# dot-reader.net
KiCad netlist of a schematic drawn in EAGLE
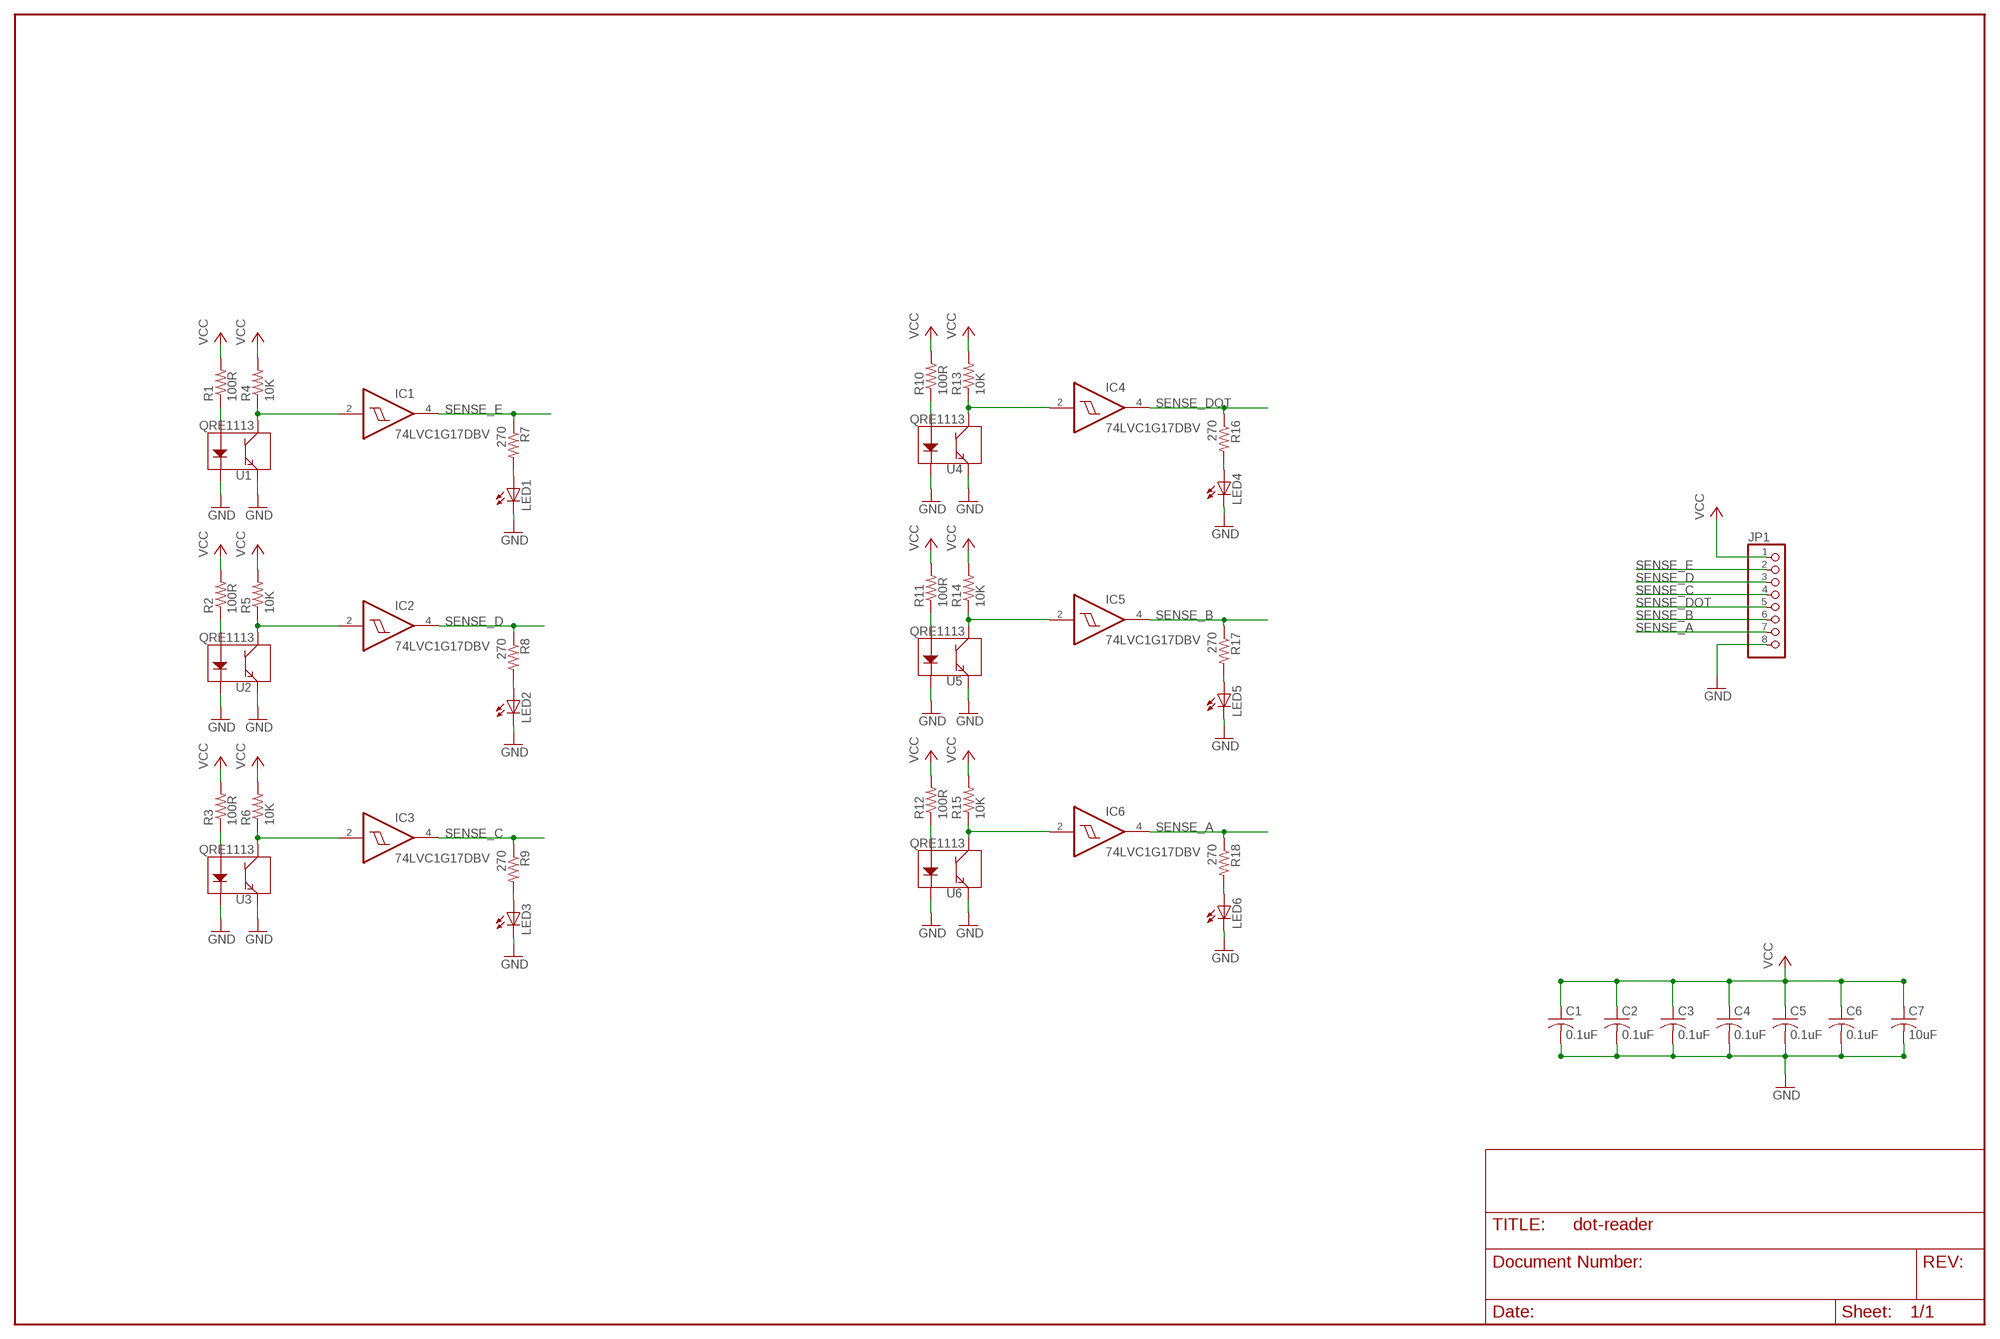
[diagram p0: schematic, sheet 1]

(export (version "E")
  (design (tool "Eeschema 10.0.6"))
  (components
    (comp (ref "C1")
      (value "0.1uF")
      (footprint "eagle-import:C0603")
      (libsource (lib "eagle-import") (part "C-USC0603"))
    )
    (comp (ref "C2")
      (value "0.1uF")
      (footprint "eagle-import:C0603")
      (libsource (lib "eagle-import") (part "C-USC0603"))
    )
    (comp (ref "C3")
      (value "0.1uF")
      (footprint "eagle-import:C0603")
      (libsource (lib "eagle-import") (part "C-USC0603"))
    )
    (comp (ref "C4")
      (value "0.1uF")
      (footprint "eagle-import:C0603")
      (libsource (lib "eagle-import") (part "C-USC0603"))
    )
    (comp (ref "C5")
      (value "0.1uF")
      (footprint "eagle-import:C0603")
      (libsource (lib "eagle-import") (part "C-USC0603"))
    )
    (comp (ref "C6")
      (value "0.1uF")
      (footprint "eagle-import:C0603")
      (libsource (lib "eagle-import") (part "C-USC0603"))
    )
    (comp (ref "C7")
      (value "10uF")
      (footprint "eagle-import:C0805")
      (libsource (lib "eagle-import") (part "C-USC0805"))
    )
    (comp (ref "IC1")
      (value "74LVC1G17DBV")
      (footprint "eagle-import:SOT23-5")
      (libsource (lib "eagle-import") (part "741G17DBVLVC"))
    )
    (comp (ref "IC2")
      (value "74LVC1G17DBV")
      (footprint "eagle-import:SOT23-5")
      (libsource (lib "eagle-import") (part "741G17DBVLVC"))
    )
    (comp (ref "IC3")
      (value "74LVC1G17DBV")
      (footprint "eagle-import:SOT23-5")
      (libsource (lib "eagle-import") (part "741G17DBVLVC"))
    )
    (comp (ref "IC4")
      (value "74LVC1G17DBV")
      (footprint "eagle-import:SOT23-5")
      (libsource (lib "eagle-import") (part "741G17DBVLVC"))
    )
    (comp (ref "IC5")
      (value "74LVC1G17DBV")
      (footprint "eagle-import:SOT23-5")
      (libsource (lib "eagle-import") (part "741G17DBVLVC"))
    )
    (comp (ref "IC6")
      (value "74LVC1G17DBV")
      (footprint "eagle-import:SOT23-5")
      (libsource (lib "eagle-import") (part "741G17DBVLVC"))
    )
    (comp (ref "JP1")
      (value "PINHD-1X8")
      (footprint "eagle-import:1X08")
      (libsource (lib "eagle-import") (part "PINHD-1X8"))
    )
    (comp (ref "LED1")
      (value "LEDCHIP-LED0805")
      (footprint "eagle-import:CHIP-LED0805")
      (libsource (lib "eagle-import") (part "LEDCHIP-LED0805"))
    )
    (comp (ref "LED2")
      (value "LEDCHIP-LED0805")
      (footprint "eagle-import:CHIP-LED0805")
      (libsource (lib "eagle-import") (part "LEDCHIP-LED0805"))
    )
    (comp (ref "LED3")
      (value "LEDCHIP-LED0805")
      (footprint "eagle-import:CHIP-LED0805")
      (libsource (lib "eagle-import") (part "LEDCHIP-LED0805"))
    )
    (comp (ref "LED4")
      (value "LEDCHIP-LED0805")
      (footprint "eagle-import:CHIP-LED0805")
      (libsource (lib "eagle-import") (part "LEDCHIP-LED0805"))
    )
    (comp (ref "LED5")
      (value "LEDCHIP-LED0805")
      (footprint "eagle-import:CHIP-LED0805")
      (libsource (lib "eagle-import") (part "LEDCHIP-LED0805"))
    )
    (comp (ref "LED6")
      (value "LEDCHIP-LED0805")
      (footprint "eagle-import:CHIP-LED0805")
      (libsource (lib "eagle-import") (part "LEDCHIP-LED0805"))
    )
    (comp (ref "R1")
      (value "100R")
      (footprint "eagle-import:M0805")
      (libsource (lib "eagle-import") (part "R-US_M0805"))
    )
    (comp (ref "R2")
      (value "100R")
      (footprint "eagle-import:M0805")
      (libsource (lib "eagle-import") (part "R-US_M0805"))
    )
    (comp (ref "R3")
      (value "100R")
      (footprint "eagle-import:M0805")
      (libsource (lib "eagle-import") (part "R-US_M0805"))
    )
    (comp (ref "R4")
      (value "10K")
      (footprint "eagle-import:M0805")
      (libsource (lib "eagle-import") (part "R-US_M0805"))
    )
    (comp (ref "R5")
      (value "10K")
      (footprint "eagle-import:M0805")
      (libsource (lib "eagle-import") (part "R-US_M0805"))
    )
    (comp (ref "R6")
      (value "10K")
      (footprint "eagle-import:M0805")
      (libsource (lib "eagle-import") (part "R-US_M0805"))
    )
    (comp (ref "R7")
      (value "270")
      (footprint "eagle-import:R0805")
      (libsource (lib "eagle-import") (part "R-US_R0805"))
    )
    (comp (ref "R8")
      (value "270")
      (footprint "eagle-import:R0805")
      (libsource (lib "eagle-import") (part "R-US_R0805"))
    )
    (comp (ref "R9")
      (value "270")
      (footprint "eagle-import:R0805")
      (libsource (lib "eagle-import") (part "R-US_R0805"))
    )
    (comp (ref "R10")
      (value "100R")
      (footprint "eagle-import:M0805")
      (libsource (lib "eagle-import") (part "R-US_M0805"))
    )
    (comp (ref "R11")
      (value "100R")
      (footprint "eagle-import:M0805")
      (libsource (lib "eagle-import") (part "R-US_M0805"))
    )
    (comp (ref "R12")
      (value "100R")
      (footprint "eagle-import:M0805")
      (libsource (lib "eagle-import") (part "R-US_M0805"))
    )
    (comp (ref "R13")
      (value "10K")
      (footprint "eagle-import:M0805")
      (libsource (lib "eagle-import") (part "R-US_M0805"))
    )
    (comp (ref "R14")
      (value "10K")
      (footprint "eagle-import:M0805")
      (libsource (lib "eagle-import") (part "R-US_M0805"))
    )
    (comp (ref "R15")
      (value "10K")
      (footprint "eagle-import:M0805")
      (libsource (lib "eagle-import") (part "R-US_M0805"))
    )
    (comp (ref "R16")
      (value "270")
      (footprint "eagle-import:R0805")
      (libsource (lib "eagle-import") (part "R-US_R0805"))
    )
    (comp (ref "R17")
      (value "270")
      (footprint "eagle-import:R0805")
      (libsource (lib "eagle-import") (part "R-US_R0805"))
    )
    (comp (ref "R18")
      (value "270")
      (footprint "eagle-import:R0805")
      (libsource (lib "eagle-import") (part "R-US_R0805"))
    )
    (comp (ref "U1")
      (value "QRE1113")
      (footprint "eagle-import:QRE1113")
      (libsource (lib "eagle-import") (part "QRE1113"))
    )
    (comp (ref "U2")
      (value "QRE1113")
      (footprint "eagle-import:QRE1113")
      (libsource (lib "eagle-import") (part "QRE1113"))
    )
    (comp (ref "U3")
      (value "QRE1113")
      (footprint "eagle-import:QRE1113")
      (libsource (lib "eagle-import") (part "QRE1113"))
    )
    (comp (ref "U4")
      (value "QRE1113")
      (footprint "eagle-import:QRE1113")
      (libsource (lib "eagle-import") (part "QRE1113"))
    )
    (comp (ref "U5")
      (value "QRE1113")
      (footprint "eagle-import:QRE1113")
      (libsource (lib "eagle-import") (part "QRE1113"))
    )
    (comp (ref "U6")
      (value "QRE1113")
      (footprint "eagle-import:QRE1113")
      (libsource (lib "eagle-import") (part "QRE1113"))
    )
  )
  (nets
    (net (code "1") (name "/SENSE_A") (class "Default")
      (node (ref "IC6") (pin "4") (pinfunction "O_4") (pintype "output"))
      (node (ref "JP1") (pin "7") (pinfunction "7_7") (pintype "passive"))
      (node (ref "R18") (pin "1") (pinfunction "1_1") (pintype "passive"))
    )
    (net (code "2") (name "/SENSE_B") (class "Default")
      (node (ref "IC5") (pin "4") (pinfunction "O_4") (pintype "output"))
      (node (ref "JP1") (pin "6") (pinfunction "6_6") (pintype "passive"))
      (node (ref "R17") (pin "1") (pinfunction "1_1") (pintype "passive"))
    )
    (net (code "3") (name "/SENSE_C") (class "Default")
      (node (ref "IC3") (pin "4") (pinfunction "O_4") (pintype "output"))
      (node (ref "JP1") (pin "4") (pinfunction "4_4") (pintype "passive"))
      (node (ref "R9") (pin "1") (pinfunction "1_1") (pintype "passive"))
    )
    (net (code "4") (name "/SENSE_D") (class "Default")
      (node (ref "IC2") (pin "4") (pinfunction "O_4") (pintype "output"))
      (node (ref "JP1") (pin "3") (pinfunction "3_3") (pintype "passive"))
      (node (ref "R8") (pin "1") (pinfunction "1_1") (pintype "passive"))
    )
    (net (code "5") (name "/SENSE_DOT") (class "Default")
      (node (ref "IC4") (pin "4") (pinfunction "O_4") (pintype "output"))
      (node (ref "JP1") (pin "5") (pinfunction "5_5") (pintype "passive"))
      (node (ref "R16") (pin "1") (pinfunction "1_1") (pintype "passive"))
    )
    (net (code "6") (name "/SENSE_E") (class "Default")
      (node (ref "IC1") (pin "4") (pinfunction "O_4") (pintype "output"))
      (node (ref "JP1") (pin "2") (pinfunction "2_2") (pintype "passive"))
      (node (ref "R7") (pin "1") (pinfunction "1_1") (pintype "passive"))
    )
    (net (code "7") (name "GND") (class "Default")
      (node (ref "C1") (pin "2") (pinfunction "2_2") (pintype "passive"))
      (node (ref "C2") (pin "2") (pinfunction "2_2") (pintype "passive"))
      (node (ref "C3") (pin "2") (pinfunction "2_2") (pintype "passive"))
      (node (ref "C4") (pin "2") (pinfunction "2_2") (pintype "passive"))
      (node (ref "C5") (pin "2") (pinfunction "2_2") (pintype "passive"))
      (node (ref "C6") (pin "2") (pinfunction "2_2") (pintype "passive"))
      (node (ref "C7") (pin "2") (pinfunction "2_2") (pintype "passive"))
      (node (ref "JP1") (pin "8") (pinfunction "8_8") (pintype "passive"))
      (node (ref "LED1") (pin "C") (pinfunction "C_C") (pintype "passive"))
      (node (ref "LED2") (pin "C") (pinfunction "C_C") (pintype "passive"))
      (node (ref "LED3") (pin "C") (pinfunction "C_C") (pintype "passive"))
      (node (ref "LED4") (pin "C") (pinfunction "C_C") (pintype "passive"))
      (node (ref "LED5") (pin "C") (pinfunction "C_C") (pintype "passive"))
      (node (ref "LED6") (pin "C") (pinfunction "C_C") (pintype "passive"))
      (node (ref "U1") (pin "2") (pinfunction "K_2") (pintype "bidirectional"))
      (node (ref "U1") (pin "4") (pinfunction "E_4") (pintype "bidirectional"))
      (node (ref "U2") (pin "2") (pinfunction "K_2") (pintype "bidirectional"))
      (node (ref "U2") (pin "4") (pinfunction "E_4") (pintype "bidirectional"))
      (node (ref "U3") (pin "2") (pinfunction "K_2") (pintype "bidirectional"))
      (node (ref "U3") (pin "4") (pinfunction "E_4") (pintype "bidirectional"))
      (node (ref "U4") (pin "2") (pinfunction "K_2") (pintype "bidirectional"))
      (node (ref "U4") (pin "4") (pinfunction "E_4") (pintype "bidirectional"))
      (node (ref "U5") (pin "2") (pinfunction "K_2") (pintype "bidirectional"))
      (node (ref "U5") (pin "4") (pinfunction "E_4") (pintype "bidirectional"))
      (node (ref "U6") (pin "2") (pinfunction "K_2") (pintype "bidirectional"))
      (node (ref "U6") (pin "4") (pinfunction "E_4") (pintype "bidirectional"))
    )
    (net (code "8") (name "Net-(IC1A-I)") (class "Default")
      (node (ref "IC1") (pin "2") (pinfunction "I_2") (pintype "input"))
      (node (ref "R4") (pin "1") (pinfunction "1_1") (pintype "passive"))
      (node (ref "U1") (pin "3") (pinfunction "C_3") (pintype "bidirectional"))
    )
    (net (code "9") (name "Net-(IC2A-I)") (class "Default")
      (node (ref "IC2") (pin "2") (pinfunction "I_2") (pintype "input"))
      (node (ref "R5") (pin "1") (pinfunction "1_1") (pintype "passive"))
      (node (ref "U2") (pin "3") (pinfunction "C_3") (pintype "bidirectional"))
    )
    (net (code "10") (name "Net-(IC3A-I)") (class "Default")
      (node (ref "IC3") (pin "2") (pinfunction "I_2") (pintype "input"))
      (node (ref "R6") (pin "1") (pinfunction "1_1") (pintype "passive"))
      (node (ref "U3") (pin "3") (pinfunction "C_3") (pintype "bidirectional"))
    )
    (net (code "11") (name "Net-(IC4A-I)") (class "Default")
      (node (ref "IC4") (pin "2") (pinfunction "I_2") (pintype "input"))
      (node (ref "R13") (pin "1") (pinfunction "1_1") (pintype "passive"))
      (node (ref "U4") (pin "3") (pinfunction "C_3") (pintype "bidirectional"))
    )
    (net (code "12") (name "Net-(IC5A-I)") (class "Default")
      (node (ref "IC5") (pin "2") (pinfunction "I_2") (pintype "input"))
      (node (ref "R14") (pin "1") (pinfunction "1_1") (pintype "passive"))
      (node (ref "U5") (pin "3") (pinfunction "C_3") (pintype "bidirectional"))
    )
    (net (code "13") (name "Net-(IC6A-I)") (class "Default")
      (node (ref "IC6") (pin "2") (pinfunction "I_2") (pintype "input"))
      (node (ref "R15") (pin "1") (pinfunction "1_1") (pintype "passive"))
      (node (ref "U6") (pin "3") (pinfunction "C_3") (pintype "bidirectional"))
    )
    (net (code "14") (name "Net-(LED1-PadA)") (class "Default")
      (node (ref "LED1") (pin "A") (pinfunction "A_A") (pintype "passive"))
      (node (ref "R7") (pin "2") (pinfunction "2_2") (pintype "passive"))
    )
    (net (code "15") (name "Net-(LED2-PadA)") (class "Default")
      (node (ref "LED2") (pin "A") (pinfunction "A_A") (pintype "passive"))
      (node (ref "R8") (pin "2") (pinfunction "2_2") (pintype "passive"))
    )
    (net (code "16") (name "Net-(LED3-PadA)") (class "Default")
      (node (ref "LED3") (pin "A") (pinfunction "A_A") (pintype "passive"))
      (node (ref "R9") (pin "2") (pinfunction "2_2") (pintype "passive"))
    )
    (net (code "17") (name "Net-(LED4-PadA)") (class "Default")
      (node (ref "LED4") (pin "A") (pinfunction "A_A") (pintype "passive"))
      (node (ref "R16") (pin "2") (pinfunction "2_2") (pintype "passive"))
    )
    (net (code "18") (name "Net-(LED5-PadA)") (class "Default")
      (node (ref "LED5") (pin "A") (pinfunction "A_A") (pintype "passive"))
      (node (ref "R17") (pin "2") (pinfunction "2_2") (pintype "passive"))
    )
    (net (code "19") (name "Net-(LED6-PadA)") (class "Default")
      (node (ref "LED6") (pin "A") (pinfunction "A_A") (pintype "passive"))
      (node (ref "R18") (pin "2") (pinfunction "2_2") (pintype "passive"))
    )
    (net (code "20") (name "Net-(U1-A)") (class "Default")
      (node (ref "R1") (pin "1") (pinfunction "1_1") (pintype "passive"))
      (node (ref "U1") (pin "1") (pinfunction "A_1") (pintype "bidirectional"))
    )
    (net (code "21") (name "Net-(U2-A)") (class "Default")
      (node (ref "R2") (pin "1") (pinfunction "1_1") (pintype "passive"))
      (node (ref "U2") (pin "1") (pinfunction "A_1") (pintype "bidirectional"))
    )
    (net (code "22") (name "Net-(U3-A)") (class "Default")
      (node (ref "R3") (pin "1") (pinfunction "1_1") (pintype "passive"))
      (node (ref "U3") (pin "1") (pinfunction "A_1") (pintype "bidirectional"))
    )
    (net (code "23") (name "Net-(U4-A)") (class "Default")
      (node (ref "R10") (pin "1") (pinfunction "1_1") (pintype "passive"))
      (node (ref "U4") (pin "1") (pinfunction "A_1") (pintype "bidirectional"))
    )
    (net (code "24") (name "Net-(U5-A)") (class "Default")
      (node (ref "R11") (pin "1") (pinfunction "1_1") (pintype "passive"))
      (node (ref "U5") (pin "1") (pinfunction "A_1") (pintype "bidirectional"))
    )
    (net (code "25") (name "Net-(U6-A)") (class "Default")
      (node (ref "R12") (pin "1") (pinfunction "1_1") (pintype "passive"))
      (node (ref "U6") (pin "1") (pinfunction "A_1") (pintype "bidirectional"))
    )
    (net (code "26") (name "VCC") (class "Default")
      (node (ref "C1") (pin "1") (pinfunction "1_1") (pintype "passive"))
      (node (ref "C2") (pin "1") (pinfunction "1_1") (pintype "passive"))
      (node (ref "C3") (pin "1") (pinfunction "1_1") (pintype "passive"))
      (node (ref "C4") (pin "1") (pinfunction "1_1") (pintype "passive"))
      (node (ref "C5") (pin "1") (pinfunction "1_1") (pintype "passive"))
      (node (ref "C6") (pin "1") (pinfunction "1_1") (pintype "passive"))
      (node (ref "C7") (pin "1") (pinfunction "1_1") (pintype "passive"))
      (node (ref "JP1") (pin "1") (pinfunction "1_1") (pintype "passive"))
      (node (ref "R1") (pin "2") (pinfunction "2_2") (pintype "passive"))
      (node (ref "R10") (pin "2") (pinfunction "2_2") (pintype "passive"))
      (node (ref "R11") (pin "2") (pinfunction "2_2") (pintype "passive"))
      (node (ref "R12") (pin "2") (pinfunction "2_2") (pintype "passive"))
      (node (ref "R13") (pin "2") (pinfunction "2_2") (pintype "passive"))
      (node (ref "R14") (pin "2") (pinfunction "2_2") (pintype "passive"))
      (node (ref "R15") (pin "2") (pinfunction "2_2") (pintype "passive"))
      (node (ref "R2") (pin "2") (pinfunction "2_2") (pintype "passive"))
      (node (ref "R3") (pin "2") (pinfunction "2_2") (pintype "passive"))
      (node (ref "R4") (pin "2") (pinfunction "2_2") (pintype "passive"))
      (node (ref "R5") (pin "2") (pinfunction "2_2") (pintype "passive"))
      (node (ref "R6") (pin "2") (pinfunction "2_2") (pintype "passive"))
    )
  )
)
